# Motherboard_schematic.net
KiCad netlist of a schematic drawn in Altium Designer
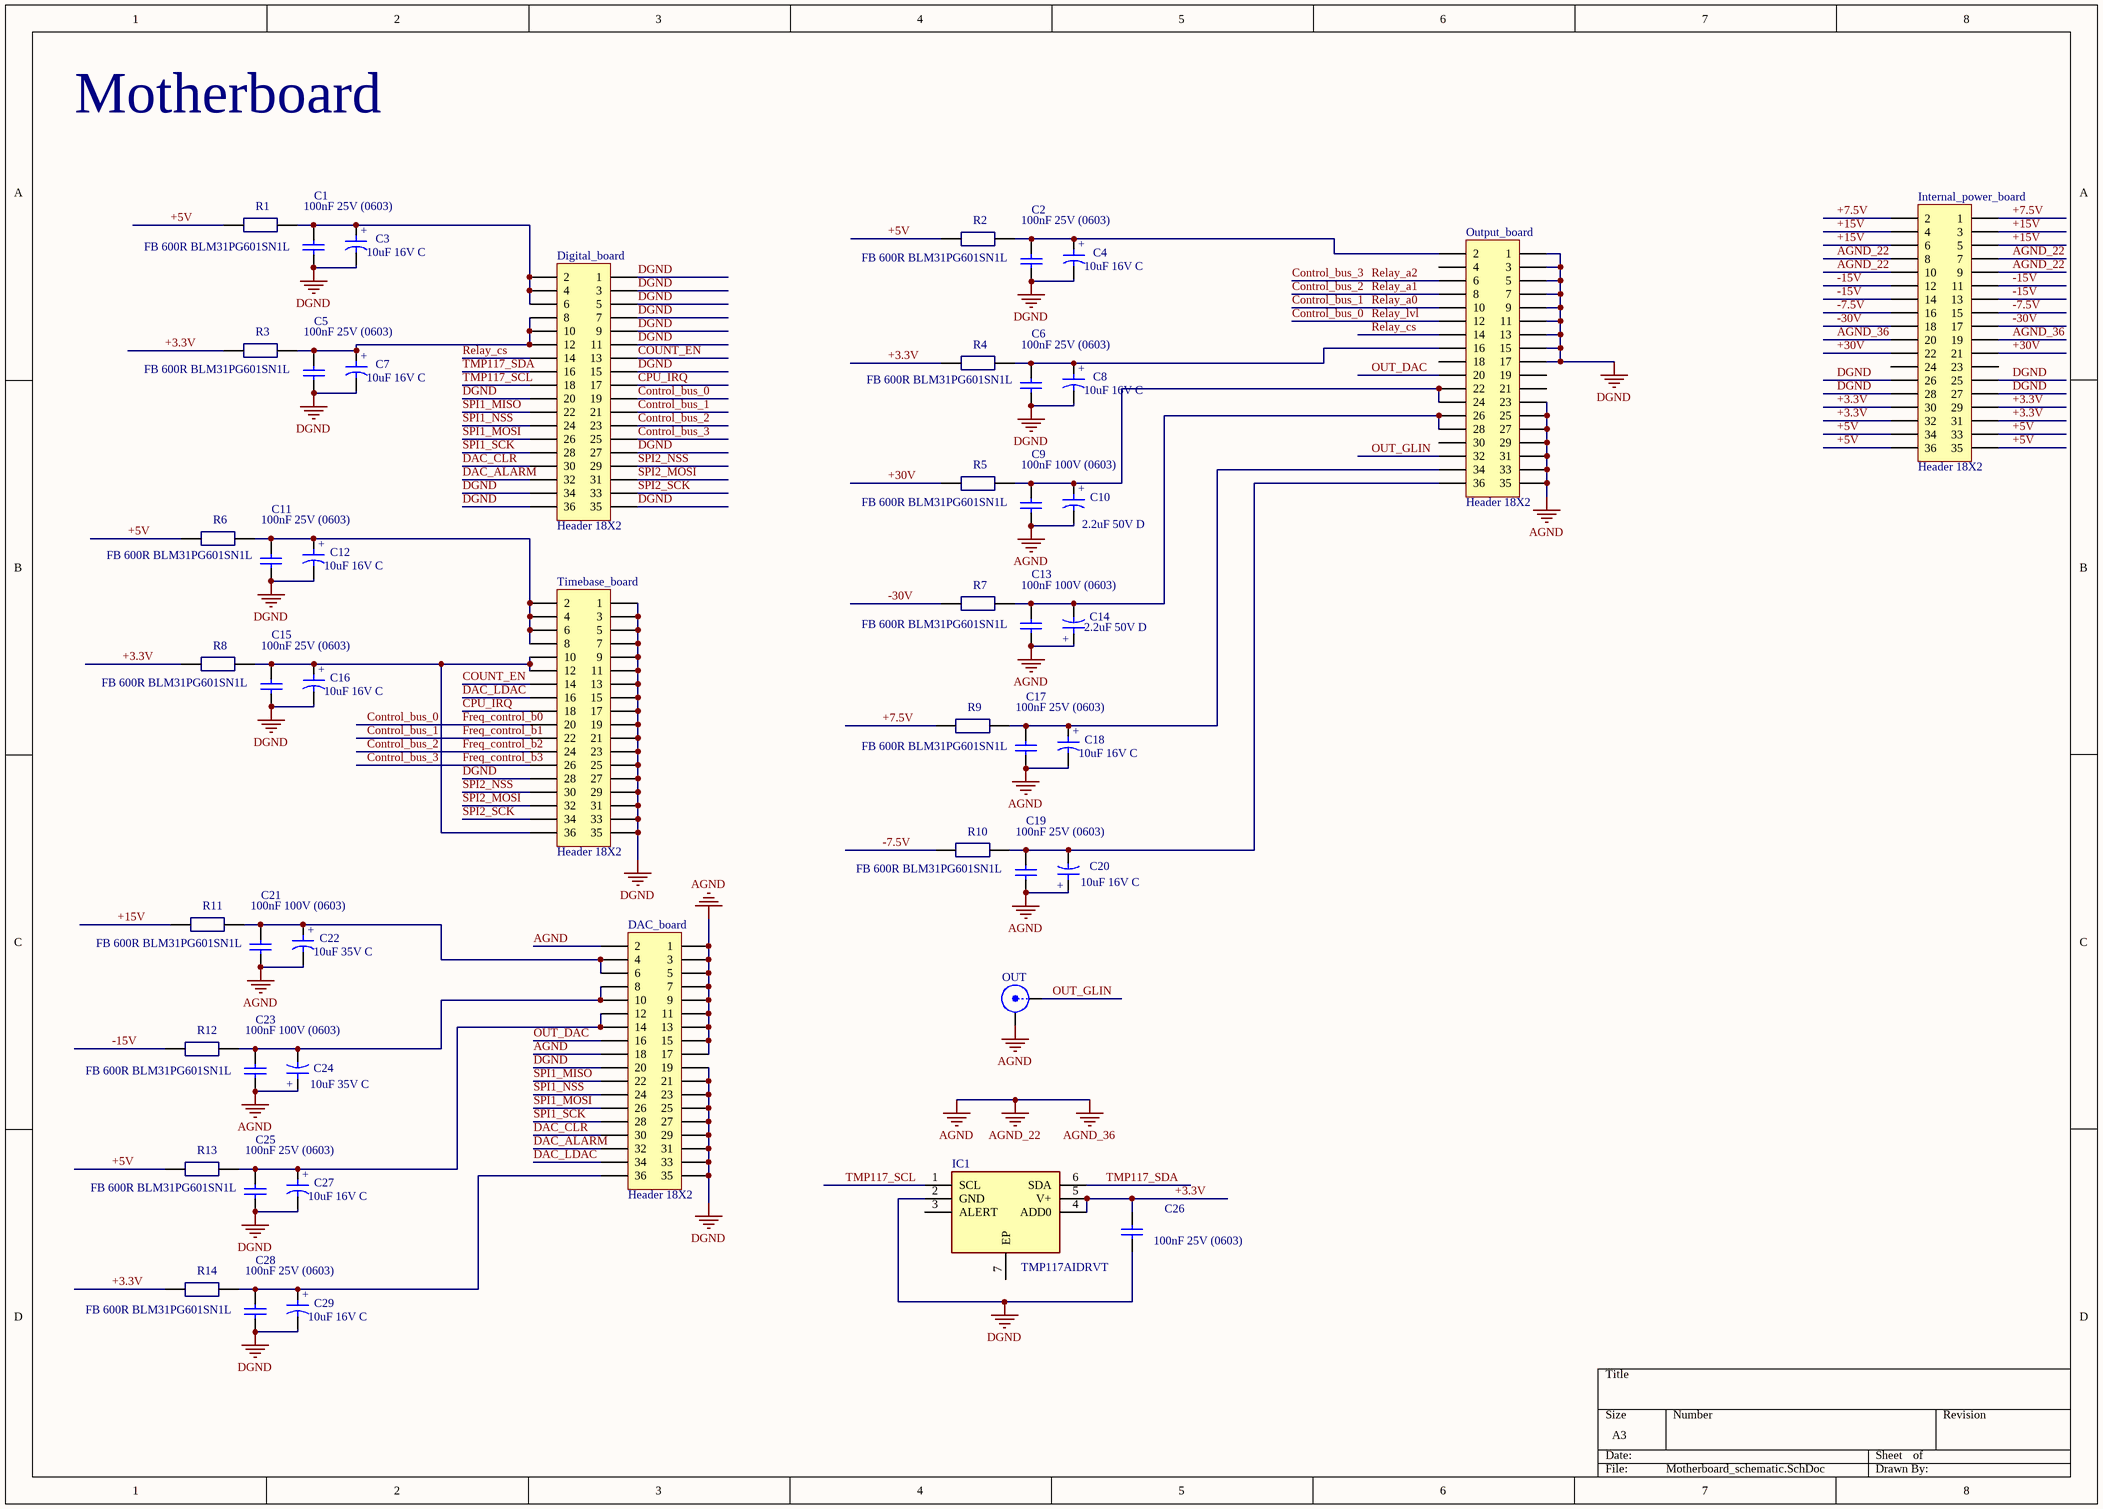
[diagram p0: Motherboard_schematic.SchDoc]

(export (version "E")
  (design (tool "Eeschema 10.0.6"))
  (components
    (comp (ref "C1")
      (value "100nF 25V (0603)")
      (footprint "CAP 0603")
      (description "Capacitor (Semiconductor SIM Model)")
      (fields (field (name "PUBLISHER") "Altium Limited"))
      (libsource (lib "Miscellaneous Devices") (part "Cap Semi"))
    )
    (comp (ref "C2")
      (value "100nF 25V (0603)")
      (footprint "CAP 0603")
      (description "Capacitor (Semiconductor SIM Model)")
      (fields (field (name "PUBLISHER") "Altium Limited"))
      (libsource (lib "Miscellaneous Devices") (part "Cap Semi"))
    )
    (comp (ref "C3")
      (value "10uF 16V C")
      (footprint "CAPMP6032X280N")
      (description "Polarised capacitor")
      (fields
        (field (name "PART NUMBER") "CTE6032-28_10UF_25V_10%_LESR0500")
        (field (name "VOLTAGE") "25V")
        (field (name "AUTHOR") "CERN DEM JLC")
      )
      (libsource (lib "Capacitors") (part "Capacitor - polarized"))
    )
    (comp (ref "C4")
      (value "10uF 16V C")
      (footprint "CAPMP6032X280N")
      (description "Polarised capacitor")
      (fields
        (field (name "PART NUMBER") "CTE6032-28_10UF_25V_10%_LESR0500")
        (field (name "VOLTAGE") "25V")
        (field (name "AUTHOR") "CERN DEM JLC")
      )
      (libsource (lib "Capacitors") (part "Capacitor - polarized"))
    )
    (comp (ref "C5")
      (value "100nF 25V (0603)")
      (footprint "CAP 0603")
      (description "Capacitor (Semiconductor SIM Model)")
      (fields (field (name "PUBLISHER") "Altium Limited"))
      (libsource (lib "Miscellaneous Devices") (part "Cap Semi"))
    )
    (comp (ref "C6")
      (value "100nF 25V (0603)")
      (footprint "CAP 0603")
      (description "Capacitor (Semiconductor SIM Model)")
      (fields (field (name "PUBLISHER") "Altium Limited"))
      (libsource (lib "Miscellaneous Devices") (part "Cap Semi"))
    )
    (comp (ref "C7")
      (value "10uF 16V C")
      (footprint "CAPMP6032X280N")
      (description "Polarised capacitor")
      (fields
        (field (name "PART NUMBER") "CTE6032-28_10UF_25V_10%_LESR0500")
        (field (name "VOLTAGE") "25V")
        (field (name "AUTHOR") "CERN DEM JLC")
      )
      (libsource (lib "Capacitors") (part "Capacitor - polarized"))
    )
    (comp (ref "C8")
      (value "10uF 16V C")
      (footprint "CAPMP6032X280N")
      (description "Polarised capacitor")
      (fields
        (field (name "PART NUMBER") "CTE6032-28_10UF_25V_10%_LESR0500")
        (field (name "VOLTAGE") "25V")
        (field (name "AUTHOR") "CERN DEM JLC")
      )
      (libsource (lib "Capacitors") (part "Capacitor - polarized"))
    )
    (comp (ref "C9")
      (value "100nF 100V (0603)")
      (footprint "CAP 0603")
      (description "Capacitor (Semiconductor SIM Model)")
      (fields (field (name "PUBLISHER") "Altium Limited"))
      (libsource (lib "Miscellaneous Devices") (part "Cap Semi"))
    )
    (comp (ref "C10")
      (value "2.2uF 50V D")
      (footprint "CAPMP7343X310N")
      (description "Polarised capacitor")
      (fields
        (field (name "PART NUMBER") "CTE7343-31_22UF_35V_20%_LESR0400")
        (field (name "VOLTAGE") "35V")
        (field (name "AUTHOR") "CERN DEM MR")
      )
      (libsource (lib "Capacitors") (part "Capacitor - polarized"))
    )
    (comp (ref "C11")
      (value "100nF 25V (0603)")
      (footprint "CAP 0603")
      (description "Capacitor (Semiconductor SIM Model)")
      (fields (field (name "PUBLISHER") "Altium Limited"))
      (libsource (lib "Miscellaneous Devices") (part "Cap Semi"))
    )
    (comp (ref "C12")
      (value "10uF 16V C")
      (footprint "CAPMP6032X280N")
      (description "Polarised capacitor")
      (fields
        (field (name "PART NUMBER") "CTE6032-28_10UF_25V_10%_LESR0500")
        (field (name "VOLTAGE") "25V")
        (field (name "AUTHOR") "CERN DEM JLC")
      )
      (libsource (lib "Capacitors") (part "Capacitor - polarized"))
    )
    (comp (ref "C13")
      (value "100nF 100V (0603)")
      (footprint "CAP 0603")
      (description "Capacitor (Semiconductor SIM Model)")
      (fields (field (name "PUBLISHER") "Altium Limited"))
      (libsource (lib "Miscellaneous Devices") (part "Cap Semi"))
    )
    (comp (ref "C14")
      (value "2.2uF 50V D")
      (footprint "CAPMP7343X310N")
      (description "Polarised capacitor")
      (fields
        (field (name "PART NUMBER") "CTE7343-31_22UF_35V_20%_LESR0400")
        (field (name "VOLTAGE") "35V")
        (field (name "AUTHOR") "CERN DEM MR")
      )
      (libsource (lib "Capacitors") (part "Capacitor - polarized"))
    )
    (comp (ref "C15")
      (value "100nF 25V (0603)")
      (footprint "CAP 0603")
      (description "Capacitor (Semiconductor SIM Model)")
      (fields (field (name "PUBLISHER") "Altium Limited"))
      (libsource (lib "Miscellaneous Devices") (part "Cap Semi"))
    )
    (comp (ref "C16")
      (value "10uF 16V C")
      (footprint "CAPMP6032X280N")
      (description "Polarised capacitor")
      (fields
        (field (name "PART NUMBER") "CTE6032-28_10UF_25V_10%_LESR0500")
        (field (name "VOLTAGE") "25V")
        (field (name "AUTHOR") "CERN DEM JLC")
      )
      (libsource (lib "Capacitors") (part "Capacitor - polarized"))
    )
    (comp (ref "C17")
      (value "100nF 25V (0603)")
      (footprint "CAP 0603")
      (description "Capacitor (Semiconductor SIM Model)")
      (fields (field (name "PUBLISHER") "Altium Limited"))
      (libsource (lib "Miscellaneous Devices") (part "Cap Semi"))
    )
    (comp (ref "C18")
      (value "10uF 16V C")
      (footprint "CAPMP6032X280N")
      (description "Polarised capacitor")
      (fields
        (field (name "PART NUMBER") "CTE6032-28_10UF_25V_10%_LESR0500")
        (field (name "VOLTAGE") "25V")
        (field (name "AUTHOR") "CERN DEM JLC")
      )
      (libsource (lib "Capacitors") (part "Capacitor - polarized"))
    )
    (comp (ref "C19")
      (value "100nF 25V (0603)")
      (footprint "CAP 0603")
      (description "Capacitor (Semiconductor SIM Model)")
      (fields (field (name "PUBLISHER") "Altium Limited"))
      (libsource (lib "Miscellaneous Devices") (part "Cap Semi"))
    )
    (comp (ref "C20")
      (value "10uF 16V C")
      (footprint "CAPMP6032X280N")
      (description "Polarised capacitor")
      (fields
        (field (name "PART NUMBER") "CTE6032-28_10UF_25V_10%_LESR0500")
        (field (name "VOLTAGE") "25V")
        (field (name "AUTHOR") "CERN DEM JLC")
      )
      (libsource (lib "Capacitors") (part "Capacitor - polarized"))
    )
    (comp (ref "C21")
      (value "100nF 100V (0603)")
      (footprint "CAP 0603")
      (description "Capacitor (Semiconductor SIM Model)")
      (fields (field (name "PUBLISHER") "Altium Limited"))
      (libsource (lib "Miscellaneous Devices") (part "Cap Semi"))
    )
    (comp (ref "C22")
      (value "10uF 35V C")
      (footprint "CAPMP6032X280N")
      (description "Polarised capacitor")
      (fields
        (field (name "PART NUMBER") "CTE6032-28_10UF_25V_10%_LESR0500")
        (field (name "VOLTAGE") "25V")
        (field (name "AUTHOR") "CERN DEM JLC")
      )
      (libsource (lib "Capacitors") (part "Capacitor - polarized"))
    )
    (comp (ref "C23")
      (value "100nF 100V (0603)")
      (footprint "CAP 0603")
      (description "Capacitor (Semiconductor SIM Model)")
      (fields (field (name "PUBLISHER") "Altium Limited"))
      (libsource (lib "Miscellaneous Devices") (part "Cap Semi"))
    )
    (comp (ref "C24")
      (value "10uF 35V C")
      (footprint "CAPMP6032X280N")
      (description "Polarised capacitor")
      (fields
        (field (name "PART NUMBER") "CTE6032-28_10UF_25V_10%_LESR0500")
        (field (name "VOLTAGE") "25V")
        (field (name "AUTHOR") "CERN DEM JLC")
      )
      (libsource (lib "Capacitors") (part "Capacitor - polarized"))
    )
    (comp (ref "C25")
      (value "100nF 25V (0603)")
      (footprint "CAP 0603")
      (description "Capacitor (Semiconductor SIM Model)")
      (fields (field (name "PUBLISHER") "Altium Limited"))
      (libsource (lib "Miscellaneous Devices") (part "Cap Semi"))
    )
    (comp (ref "C26")
      (value "100nF 25V (0603)")
      (footprint "CAP 0603")
      (description "Capacitor (Semiconductor SIM Model)")
      (fields (field (name "PUBLISHER") "Altium Limited"))
      (libsource (lib "Miscellaneous Devices") (part "Cap Semi"))
    )
    (comp (ref "C27")
      (value "10uF 16V C")
      (footprint "CAPMP6032X280N")
      (description "Polarised capacitor")
      (fields
        (field (name "PART NUMBER") "CTE6032-28_10UF_25V_10%_LESR0500")
        (field (name "VOLTAGE") "25V")
        (field (name "AUTHOR") "CERN DEM JLC")
      )
      (libsource (lib "Capacitors") (part "Capacitor - polarized"))
    )
    (comp (ref "C28")
      (value "100nF 25V (0603)")
      (footprint "CAP 0603")
      (description "Capacitor (Semiconductor SIM Model)")
      (fields (field (name "PUBLISHER") "Altium Limited"))
      (libsource (lib "Miscellaneous Devices") (part "Cap Semi"))
    )
    (comp (ref "C29")
      (value "10uF 16V C")
      (footprint "CAPMP6032X280N")
      (description "Polarised capacitor")
      (fields
        (field (name "PART NUMBER") "CTE6032-28_10UF_25V_10%_LESR0500")
        (field (name "VOLTAGE") "25V")
        (field (name "AUTHOR") "CERN DEM JLC")
      )
      (libsource (lib "Capacitors") (part "Capacitor - polarized"))
    )
    (comp (ref "DAC_board")
      (value "Header 18X2")
      (footprint "HDR2X18")
      (description "Header, 18-Pin, Dual row")
      (fields (field (name "PUBLISHER") "Altium Limited"))
      (libsource (lib "Miscellaneous Connectors") (part "Header 18X2"))
    )
    (comp (ref "Digital_board")
      (value "Header 18X2")
      (footprint "HDR2X18")
      (description "Header, 18-Pin, Dual row")
      (fields (field (name "PUBLISHER") "Altium Limited"))
      (libsource (lib "Miscellaneous Connectors") (part "Header 18X2"))
    )
    (comp (ref "IC1")
      (value "TMP117AIDRVT")
      (footprint "SamacSys:SON65P200X200X80-7N-D")
      (description "Integrated Circuit")
      (fields (field (name "MOUSER PART NUMBER") "595-TMP117AIDRVT"))
      (libsource (lib "*") (part "TMP117AIDRVT"))
    )
    (comp (ref "Internal_power_board")
      (value "Header 18X2")
      (footprint "HDR2X18")
      (description "Header, 18-Pin, Dual row")
      (fields (field (name "PUBLISHER") "Altium Limited"))
      (libsource (lib "Miscellaneous Connectors") (part "Header 18X2"))
    )
    (comp (ref "OUT")
      (value "SMB")
      (footprint "SMB_V-RJ45")
      (description "SMB Straight Connector")
      (fields (field (name "PUBLISHER") "Altium Limited"))
      (libsource (lib "Miscellaneous Connectors") (part "SMB"))
    )
    (comp (ref "Output_board")
      (value "Header 18X2")
      (footprint "HDR2X18")
      (description "Header, 18-Pin, Dual row")
      (fields (field (name "PUBLISHER") "Altium Limited"))
      (libsource (lib "Miscellaneous Connectors") (part "Header 18X2"))
    )
    (comp (ref "R1")
      (value "FB 600R BLM31PG601SN1L")
      (footprint "C1206")
      (libsource (lib "Микрон-3") (part "Resistor 0805"))
    )
    (comp (ref "R2")
      (value "FB 600R BLM31PG601SN1L")
      (footprint "C1206")
      (libsource (lib "Микрон-3") (part "Resistor 0805"))
    )
    (comp (ref "R3")
      (value "FB 600R BLM31PG601SN1L")
      (footprint "C1206")
      (libsource (lib "Микрон-3") (part "Resistor 0805"))
    )
    (comp (ref "R4")
      (value "FB 600R BLM31PG601SN1L")
      (footprint "C1206")
      (libsource (lib "Микрон-3") (part "Resistor 0805"))
    )
    (comp (ref "R5")
      (value "FB 600R BLM31PG601SN1L")
      (footprint "C1206")
      (libsource (lib "Микрон-3") (part "Resistor 0805"))
    )
    (comp (ref "R6")
      (value "FB 600R BLM31PG601SN1L")
      (footprint "C1206")
      (libsource (lib "Микрон-3") (part "Resistor 0805"))
    )
    (comp (ref "R7")
      (value "FB 600R BLM31PG601SN1L")
      (footprint "C1206")
      (libsource (lib "Микрон-3") (part "Resistor 0805"))
    )
    (comp (ref "R8")
      (value "FB 600R BLM31PG601SN1L")
      (footprint "C1206")
      (libsource (lib "Микрон-3") (part "Resistor 0805"))
    )
    (comp (ref "R9")
      (value "FB 600R BLM31PG601SN1L")
      (footprint "C1206")
      (libsource (lib "Микрон-3") (part "Resistor 0805"))
    )
    (comp (ref "R10")
      (value "FB 600R BLM31PG601SN1L")
      (footprint "C1206")
      (libsource (lib "Микрон-3") (part "Resistor 0805"))
    )
    (comp (ref "R11")
      (value "FB 600R BLM31PG601SN1L")
      (footprint "C1206")
      (libsource (lib "Микрон-3") (part "Resistor 0805"))
    )
    (comp (ref "R12")
      (value "FB 600R BLM31PG601SN1L")
      (footprint "C1206")
      (libsource (lib "Микрон-3") (part "Resistor 0805"))
    )
    (comp (ref "R13")
      (value "FB 600R BLM31PG601SN1L")
      (footprint "C1206")
      (libsource (lib "Микрон-3") (part "Resistor 0805"))
    )
    (comp (ref "R14")
      (value "FB 600R BLM31PG601SN1L")
      (footprint "C1206")
      (libsource (lib "Микрон-3") (part "Resistor 0805"))
    )
    (comp (ref "Timebase_board")
      (value "Header 18X2")
      (footprint "HDR2X18")
      (description "Header, 18-Pin, Dual row")
      (fields (field (name "PUBLISHER") "Altium Limited"))
      (libsource (lib "Miscellaneous Connectors") (part "Header 18X2"))
    )
  )
  (nets
    (net (code "1") (name "/+3.3V") (class "Default")
      (node (ref "C26") (pin "1") (pinfunction "1_1") (pintype "passive"))
      (node (ref "IC1") (pin "4") (pinfunction "ADD0_4") (pintype "passive"))
      (node (ref "IC1") (pin "5") (pinfunction "V+_5") (pintype "passive"))
      (node (ref "Internal_power_board") (pin "29") (pinfunction "29_29") (pintype "passive"))
      (node (ref "Internal_power_board") (pin "30") (pinfunction "30_30") (pintype "passive"))
      (node (ref "Internal_power_board") (pin "31") (pinfunction "31_31") (pintype "passive"))
      (node (ref "Internal_power_board") (pin "32") (pinfunction "32_32") (pintype "passive"))
      (node (ref "R14") (pin "2") (pinfunction "2_2") (pintype "passive"))
      (node (ref "R3") (pin "2") (pinfunction "2_2") (pintype "passive"))
      (node (ref "R4") (pin "2") (pinfunction "2_2") (pintype "passive"))
      (node (ref "R8") (pin "2") (pinfunction "2_2") (pintype "passive"))
    )
    (net (code "2") (name "/+5V") (class "Default")
      (node (ref "Internal_power_board") (pin "33") (pinfunction "33_33") (pintype "passive"))
      (node (ref "Internal_power_board") (pin "34") (pinfunction "34_34") (pintype "passive"))
      (node (ref "Internal_power_board") (pin "35") (pinfunction "35_35") (pintype "passive"))
      (node (ref "Internal_power_board") (pin "36") (pinfunction "36_36") (pintype "passive"))
      (node (ref "R1") (pin "2") (pinfunction "2_2") (pintype "passive"))
      (node (ref "R13") (pin "2") (pinfunction "2_2") (pintype "passive"))
      (node (ref "R2") (pin "2") (pinfunction "2_2") (pintype "passive"))
      (node (ref "R6") (pin "2") (pinfunction "2_2") (pintype "passive"))
    )
    (net (code "3") (name "/+7.5V") (class "Default")
      (node (ref "Internal_power_board") (pin "1") (pinfunction "1_1") (pintype "passive"))
      (node (ref "Internal_power_board") (pin "2") (pinfunction "2_2") (pintype "passive"))
      (node (ref "R9") (pin "2") (pinfunction "2_2") (pintype "passive"))
    )
    (net (code "4") (name "/+15V") (class "Default")
      (node (ref "Internal_power_board") (pin "3") (pinfunction "3_3") (pintype "passive"))
      (node (ref "Internal_power_board") (pin "4") (pinfunction "4_4") (pintype "passive"))
      (node (ref "Internal_power_board") (pin "5") (pinfunction "5_5") (pintype "passive"))
      (node (ref "Internal_power_board") (pin "6") (pinfunction "6_6") (pintype "passive"))
      (node (ref "R11") (pin "2") (pinfunction "2_2") (pintype "passive"))
    )
    (net (code "5") (name "/+30V") (class "Default")
      (node (ref "Internal_power_board") (pin "21") (pinfunction "21_21") (pintype "passive"))
      (node (ref "Internal_power_board") (pin "22") (pinfunction "22_22") (pintype "passive"))
      (node (ref "R5") (pin "2") (pinfunction "2_2") (pintype "passive"))
    )
    (net (code "6") (name "/-7.5V") (class "Default")
      (node (ref "Internal_power_board") (pin "15") (pinfunction "15_15") (pintype "passive"))
      (node (ref "Internal_power_board") (pin "16") (pinfunction "16_16") (pintype "passive"))
      (node (ref "R10") (pin "2") (pinfunction "2_2") (pintype "passive"))
    )
    (net (code "7") (name "/-15V") (class "Default")
      (node (ref "Internal_power_board") (pin "11") (pinfunction "11_11") (pintype "passive"))
      (node (ref "Internal_power_board") (pin "12") (pinfunction "12_12") (pintype "passive"))
      (node (ref "Internal_power_board") (pin "13") (pinfunction "13_13") (pintype "passive"))
      (node (ref "Internal_power_board") (pin "14") (pinfunction "14_14") (pintype "passive"))
      (node (ref "R12") (pin "2") (pinfunction "2_2") (pintype "passive"))
    )
    (net (code "8") (name "/-30V") (class "Default")
      (node (ref "Internal_power_board") (pin "17") (pinfunction "17_17") (pintype "passive"))
      (node (ref "Internal_power_board") (pin "18") (pinfunction "18_18") (pintype "passive"))
      (node (ref "R7") (pin "2") (pinfunction "2_2") (pintype "passive"))
    )
    (net (code "9") (name "/COUNT_EN") (class "Default")
      (node (ref "Digital_board") (pin "13") (pinfunction "13_13") (pintype "passive"))
      (node (ref "Timebase_board") (pin "14") (pinfunction "14_14") (pintype "passive"))
    )
    (net (code "10") (name "/CPU_IRQ") (class "Default")
      (node (ref "Digital_board") (pin "17") (pinfunction "17_17") (pintype "passive"))
      (node (ref "Timebase_board") (pin "18") (pinfunction "18_18") (pintype "passive"))
    )
    (net (code "11") (name "/Control_bus_0") (class "Default")
      (node (ref "Digital_board") (pin "19") (pinfunction "19_19") (pintype "passive"))
      (node (ref "Output_board") (pin "12") (pinfunction "12_12") (pintype "passive"))
      (node (ref "Timebase_board") (pin "20") (pinfunction "20_20") (pintype "passive"))
    )
    (net (code "12") (name "/Control_bus_1") (class "Default")
      (node (ref "Digital_board") (pin "21") (pinfunction "21_21") (pintype "passive"))
      (node (ref "Output_board") (pin "10") (pinfunction "10_10") (pintype "passive"))
      (node (ref "Timebase_board") (pin "22") (pinfunction "22_22") (pintype "passive"))
    )
    (net (code "13") (name "/Control_bus_2") (class "Default")
      (node (ref "Digital_board") (pin "23") (pinfunction "23_23") (pintype "passive"))
      (node (ref "Output_board") (pin "8") (pinfunction "8_8") (pintype "passive"))
      (node (ref "Timebase_board") (pin "24") (pinfunction "24_24") (pintype "passive"))
    )
    (net (code "14") (name "/Control_bus_3") (class "Default")
      (node (ref "Digital_board") (pin "25") (pinfunction "25_25") (pintype "passive"))
      (node (ref "Output_board") (pin "6") (pinfunction "6_6") (pintype "passive"))
      (node (ref "Timebase_board") (pin "26") (pinfunction "26_26") (pintype "passive"))
    )
    (net (code "15") (name "/DAC_ALARM") (class "Default")
      (node (ref "DAC_board") (pin "32") (pinfunction "32_32") (pintype "passive"))
      (node (ref "Digital_board") (pin "32") (pinfunction "32_32") (pintype "passive"))
    )
    (net (code "16") (name "/DAC_CLR") (class "Default")
      (node (ref "DAC_board") (pin "30") (pinfunction "30_30") (pintype "passive"))
      (node (ref "Digital_board") (pin "30") (pinfunction "30_30") (pintype "passive"))
    )
    (net (code "17") (name "/DAC_LDAC") (class "Default")
      (node (ref "DAC_board") (pin "34") (pinfunction "34_34") (pintype "passive"))
      (node (ref "Timebase_board") (pin "16") (pinfunction "16_16") (pintype "passive"))
    )
    (net (code "18") (name "/OUT_DAC") (class "Default")
      (node (ref "DAC_board") (pin "16") (pinfunction "16_16") (pintype "passive"))
      (node (ref "Output_board") (pin "20") (pinfunction "20_20") (pintype "passive"))
    )
    (net (code "19") (name "/OUT_GLIN") (class "Default")
      (node (ref "OUT") (pin "1") (pinfunction "X_1") (pintype "passive"))
      (node (ref "Output_board") (pin "32") (pinfunction "32_32") (pintype "passive"))
    )
    (net (code "20") (name "/Relay_cs") (class "Default")
      (node (ref "Digital_board") (pin "14") (pinfunction "14_14") (pintype "passive"))
      (node (ref "Output_board") (pin "14") (pinfunction "14_14") (pintype "passive"))
    )
    (net (code "21") (name "/SPI1_MISO") (class "Default")
      (node (ref "DAC_board") (pin "22") (pinfunction "22_22") (pintype "passive"))
      (node (ref "Digital_board") (pin "22") (pinfunction "22_22") (pintype "passive"))
    )
    (net (code "22") (name "/SPI1_MOSI") (class "Default")
      (node (ref "DAC_board") (pin "26") (pinfunction "26_26") (pintype "passive"))
      (node (ref "Digital_board") (pin "26") (pinfunction "26_26") (pintype "passive"))
    )
    (net (code "23") (name "/SPI1_NSS") (class "Default")
      (node (ref "DAC_board") (pin "24") (pinfunction "24_24") (pintype "passive"))
      (node (ref "Digital_board") (pin "24") (pinfunction "24_24") (pintype "passive"))
    )
    (net (code "24") (name "/SPI1_SCK") (class "Default")
      (node (ref "DAC_board") (pin "28") (pinfunction "28_28") (pintype "passive"))
      (node (ref "Digital_board") (pin "28") (pinfunction "28_28") (pintype "passive"))
    )
    (net (code "25") (name "/SPI2_MOSI") (class "Default")
      (node (ref "Digital_board") (pin "31") (pinfunction "31_31") (pintype "passive"))
      (node (ref "Timebase_board") (pin "32") (pinfunction "32_32") (pintype "passive"))
    )
    (net (code "26") (name "/SPI2_NSS") (class "Default")
      (node (ref "Digital_board") (pin "29") (pinfunction "29_29") (pintype "passive"))
      (node (ref "Timebase_board") (pin "30") (pinfunction "30_30") (pintype "passive"))
    )
    (net (code "27") (name "/SPI2_SCK") (class "Default")
      (node (ref "Digital_board") (pin "33") (pinfunction "33_33") (pintype "passive"))
      (node (ref "Timebase_board") (pin "34") (pinfunction "34_34") (pintype "passive"))
    )
    (net (code "28") (name "/TMP117_SCL") (class "Default")
      (node (ref "Digital_board") (pin "18") (pinfunction "18_18") (pintype "passive"))
      (node (ref "IC1") (pin "1") (pinfunction "SCL_1") (pintype "passive"))
    )
    (net (code "29") (name "/TMP117_SDA") (class "Default")
      (node (ref "Digital_board") (pin "16") (pinfunction "16_16") (pintype "passive"))
      (node (ref "IC1") (pin "6") (pinfunction "SDA_6") (pintype "passive"))
    )
    (net (code "30") (name "AGND") (class "Default")
      (node (ref "C10") (pin "2") (pinfunction "2_2") (pintype "passive"))
      (node (ref "C13") (pin "2") (pinfunction "2_2") (pintype "passive"))
      (node (ref "C14") (pin "1") (pinfunction "1_1") (pintype "passive"))
      (node (ref "C17") (pin "2") (pinfunction "2_2") (pintype "passive"))
      (node (ref "C18") (pin "2") (pinfunction "2_2") (pintype "passive"))
      (node (ref "C19") (pin "2") (pinfunction "2_2") (pintype "passive"))
      (node (ref "C20") (pin "1") (pinfunction "1_1") (pintype "passive"))
      (node (ref "C21") (pin "2") (pinfunction "2_2") (pintype "passive"))
      (node (ref "C22") (pin "2") (pinfunction "2_2") (pintype "passive"))
      (node (ref "C23") (pin "2") (pinfunction "2_2") (pintype "passive"))
      (node (ref "C24") (pin "1") (pinfunction "1_1") (pintype "passive"))
      (node (ref "C9") (pin "2") (pinfunction "2_2") (pintype "passive"))
      (node (ref "DAC_board") (pin "1") (pinfunction "1_1") (pintype "passive"))
      (node (ref "DAC_board") (pin "11") (pinfunction "11_11") (pintype "passive"))
      (node (ref "DAC_board") (pin "13") (pinfunction "13_13") (pintype "passive"))
      (node (ref "DAC_board") (pin "15") (pinfunction "15_15") (pintype "passive"))
      (node (ref "DAC_board") (pin "17") (pinfunction "17_17") (pintype "passive"))
      (node (ref "DAC_board") (pin "18") (pinfunction "18_18") (pintype "passive"))
      (node (ref "DAC_board") (pin "2") (pinfunction "2_2") (pintype "passive"))
      (node (ref "DAC_board") (pin "3") (pinfunction "3_3") (pintype "passive"))
      (node (ref "DAC_board") (pin "5") (pinfunction "5_5") (pintype "passive"))
      (node (ref "DAC_board") (pin "7") (pinfunction "7_7") (pintype "passive"))
      (node (ref "DAC_board") (pin "9") (pinfunction "9_9") (pintype "passive"))
      (node (ref "Internal_power_board") (pin "10") (pinfunction "10_10") (pintype "passive"))
      (node (ref "Internal_power_board") (pin "19") (pinfunction "19_19") (pintype "passive"))
      (node (ref "Internal_power_board") (pin "20") (pinfunction "20_20") (pintype "passive"))
      (node (ref "Internal_power_board") (pin "7") (pinfunction "7_7") (pintype "passive"))
      (node (ref "Internal_power_board") (pin "8") (pinfunction "8_8") (pintype "passive"))
      (node (ref "Internal_power_board") (pin "9") (pinfunction "9_9") (pintype "passive"))
      (node (ref "OUT") (pin "2") (pinfunction "Y_2") (pintype "passive"))
      (node (ref "Output_board") (pin "23") (pinfunction "23_23") (pintype "passive"))
      (node (ref "Output_board") (pin "25") (pinfunction "25_25") (pintype "passive"))
      (node (ref "Output_board") (pin "27") (pinfunction "27_27") (pintype "passive"))
      (node (ref "Output_board") (pin "29") (pinfunction "29_29") (pintype "passive"))
      (node (ref "Output_board") (pin "31") (pinfunction "31_31") (pintype "passive"))
      (node (ref "Output_board") (pin "33") (pinfunction "33_33") (pintype "passive"))
      (node (ref "Output_board") (pin "35") (pinfunction "35_35") (pintype "passive"))
    )
    (net (code "31") (name "DGND") (class "Default")
      (node (ref "C1") (pin "2") (pinfunction "2_2") (pintype "passive"))
      (node (ref "C11") (pin "2") (pinfunction "2_2") (pintype "passive"))
      (node (ref "C12") (pin "2") (pinfunction "2_2") (pintype "passive"))
      (node (ref "C15") (pin "2") (pinfunction "2_2") (pintype "passive"))
      (node (ref "C16") (pin "2") (pinfunction "2_2") (pintype "passive"))
      (node (ref "C2") (pin "2") (pinfunction "2_2") (pintype "passive"))
      (node (ref "C25") (pin "2") (pinfunction "2_2") (pintype "passive"))
      (node (ref "C26") (pin "2") (pinfunction "2_2") (pintype "passive"))
      (node (ref "C27") (pin "2") (pinfunction "2_2") (pintype "passive"))
      (node (ref "C28") (pin "2") (pinfunction "2_2") (pintype "passive"))
      (node (ref "C29") (pin "2") (pinfunction "2_2") (pintype "passive"))
      (node (ref "C3") (pin "2") (pinfunction "2_2") (pintype "passive"))
      (node (ref "C4") (pin "2") (pinfunction "2_2") (pintype "passive"))
      (node (ref "C5") (pin "2") (pinfunction "2_2") (pintype "passive"))
      (node (ref "C6") (pin "2") (pinfunction "2_2") (pintype "passive"))
      (node (ref "C7") (pin "2") (pinfunction "2_2") (pintype "passive"))
      (node (ref "C8") (pin "2") (pinfunction "2_2") (pintype "passive"))
      (node (ref "DAC_board") (pin "19") (pinfunction "19_19") (pintype "passive"))
      (node (ref "DAC_board") (pin "20") (pinfunction "20_20") (pintype "passive"))
      (node (ref "DAC_board") (pin "21") (pinfunction "21_21") (pintype "passive"))
      (node (ref "DAC_board") (pin "23") (pinfunction "23_23") (pintype "passive"))
      (node (ref "DAC_board") (pin "25") (pinfunction "25_25") (pintype "passive"))
      (node (ref "DAC_board") (pin "27") (pinfunction "27_27") (pintype "passive"))
      (node (ref "DAC_board") (pin "29") (pinfunction "29_29") (pintype "passive"))
      (node (ref "DAC_board") (pin "31") (pinfunction "31_31") (pintype "passive"))
      (node (ref "DAC_board") (pin "33") (pinfunction "33_33") (pintype "passive"))
      (node (ref "DAC_board") (pin "35") (pinfunction "35_35") (pintype "passive"))
      (node (ref "Digital_board") (pin "1") (pinfunction "1_1") (pintype "passive"))
      (node (ref "Digital_board") (pin "11") (pinfunction "11_11") (pintype "passive"))
      (node (ref "Digital_board") (pin "15") (pinfunction "15_15") (pintype "passive"))
      (node (ref "Digital_board") (pin "20") (pinfunction "20_20") (pintype "passive"))
      (node (ref "Digital_board") (pin "27") (pinfunction "27_27") (pintype "passive"))
      (node (ref "Digital_board") (pin "3") (pinfunction "3_3") (pintype "passive"))
      (node (ref "Digital_board") (pin "34") (pinfunction "34_34") (pintype "passive"))
      (node (ref "Digital_board") (pin "35") (pinfunction "35_35") (pintype "passive"))
      (node (ref "Digital_board") (pin "36") (pinfunction "36_36") (pintype "passive"))
      (node (ref "Digital_board") (pin "5") (pinfunction "5_5") (pintype "passive"))
      (node (ref "Digital_board") (pin "7") (pinfunction "7_7") (pintype "passive"))
      (node (ref "Digital_board") (pin "9") (pinfunction "9_9") (pintype "passive"))
      (node (ref "IC1") (pin "2") (pinfunction "GND_2") (pintype "passive"))
      (node (ref "Internal_power_board") (pin "25") (pinfunction "25_25") (pintype "passive"))
      (node (ref "Internal_power_board") (pin "26") (pinfunction "26_26") (pintype "passive"))
      (node (ref "Internal_power_board") (pin "27") (pinfunction "27_27") (pintype "passive"))
      (node (ref "Internal_power_board") (pin "28") (pinfunction "28_28") (pintype "passive"))
      (node (ref "Output_board") (pin "1") (pinfunction "1_1") (pintype "passive"))
      (node (ref "Output_board") (pin "11") (pinfunction "11_11") (pintype "passive"))
      (node (ref "Output_board") (pin "13") (pinfunction "13_13") (pintype "passive"))
      (node (ref "Output_board") (pin "15") (pinfunction "15_15") (pintype "passive"))
      (node (ref "Output_board") (pin "17") (pinfunction "17_17") (pintype "passive"))
      (node (ref "Output_board") (pin "3") (pinfunction "3_3") (pintype "passive"))
      (node (ref "Output_board") (pin "5") (pinfunction "5_5") (pintype "passive"))
      (node (ref "Output_board") (pin "7") (pinfunction "7_7") (pintype "passive"))
      (node (ref "Output_board") (pin "9") (pinfunction "9_9") (pintype "passive"))
      (node (ref "Timebase_board") (pin "1") (pinfunction "1_1") (pintype "passive"))
      (node (ref "Timebase_board") (pin "11") (pinfunction "11_11") (pintype "passive"))
      (node (ref "Timebase_board") (pin "13") (pinfunction "13_13") (pintype "passive"))
      (node (ref "Timebase_board") (pin "15") (pinfunction "15_15") (pintype "passive"))
      (node (ref "Timebase_board") (pin "17") (pinfunction "17_17") (pintype "passive"))
      (node (ref "Timebase_board") (pin "19") (pinfunction "19_19") (pintype "passive"))
      (node (ref "Timebase_board") (pin "21") (pinfunction "21_21") (pintype "passive"))
      (node (ref "Timebase_board") (pin "23") (pinfunction "23_23") (pintype "passive"))
      (node (ref "Timebase_board") (pin "25") (pinfunction "25_25") (pintype "passive"))
      (node (ref "Timebase_board") (pin "27") (pinfunction "27_27") (pintype "passive"))
      (node (ref "Timebase_board") (pin "28") (pinfunction "28_28") (pintype "passive"))
      (node (ref "Timebase_board") (pin "29") (pinfunction "29_29") (pintype "passive"))
      (node (ref "Timebase_board") (pin "3") (pinfunction "3_3") (pintype "passive"))
      (node (ref "Timebase_board") (pin "31") (pinfunction "31_31") (pintype "passive"))
      (node (ref "Timebase_board") (pin "33") (pinfunction "33_33") (pintype "passive"))
      (node (ref "Timebase_board") (pin "35") (pinfunction "35_35") (pintype "passive"))
      (node (ref "Timebase_board") (pin "5") (pinfunction "5_5") (pintype "passive"))
      (node (ref "Timebase_board") (pin "7") (pinfunction "7_7") (pintype "passive"))
      (node (ref "Timebase_board") (pin "9") (pinfunction "9_9") (pintype "passive"))
    )
    (net (code "32") (name "Net-(R1-A)") (class "Default")
      (node (ref "C1") (pin "1") (pinfunction "1_1") (pintype "passive"))
      (node (ref "C3") (pin "1") (pinfunction "1_1") (pintype "passive"))
      (node (ref "Digital_board") (pin "2") (pinfunction "2_2") (pintype "passive"))
      (node (ref "Digital_board") (pin "4") (pinfunction "4_4") (pintype "passive"))
      (node (ref "Digital_board") (pin "6") (pinfunction "6_6") (pintype "passive"))
      (node (ref "R1") (pin "1") (pinfunction "A_1") (pintype "passive"))
    )
    (net (code "33") (name "Net-(R2-A)") (class "Default")
      (node (ref "C2") (pin "1") (pinfunction "1_1") (pintype "passive"))
      (node (ref "C4") (pin "1") (pinfunction "1_1") (pintype "passive"))
      (node (ref "Output_board") (pin "2") (pinfunction "2_2") (pintype "passive"))
      (node (ref "R2") (pin "1") (pinfunction "A_1") (pintype "passive"))
    )
    (net (code "34") (name "Net-(R3-A)") (class "Default")
      (node (ref "C5") (pin "1") (pinfunction "1_1") (pintype "passive"))
      (node (ref "C7") (pin "1") (pinfunction "1_1") (pintype "passive"))
      (node (ref "Digital_board") (pin "10") (pinfunction "10_10") (pintype "passive"))
      (node (ref "Digital_board") (pin "12") (pinfunction "12_12") (pintype "passive"))
      (node (ref "Digital_board") (pin "8") (pinfunction "8_8") (pintype "passive"))
      (node (ref "R3") (pin "1") (pinfunction "A_1") (pintype "passive"))
    )
    (net (code "35") (name "Net-(R4-A)") (class "Default")
      (node (ref "C6") (pin "1") (pinfunction "1_1") (pintype "passive"))
      (node (ref "C8") (pin "1") (pinfunction "1_1") (pintype "passive"))
      (node (ref "Output_board") (pin "16") (pinfunction "16_16") (pintype "passive"))
      (node (ref "R4") (pin "1") (pinfunction "A_1") (pintype "passive"))
    )
    (net (code "36") (name "Net-(R5-A)") (class "Default")
      (node (ref "C10") (pin "1") (pinfunction "1_1") (pintype "passive"))
      (node (ref "C9") (pin "1") (pinfunction "1_1") (pintype "passive"))
      (node (ref "Output_board") (pin "22") (pinfunction "22_22") (pintype "passive"))
      (node (ref "Output_board") (pin "24") (pinfunction "24_24") (pintype "passive"))
      (node (ref "R5") (pin "1") (pinfunction "A_1") (pintype "passive"))
    )
    (net (code "37") (name "Net-(R6-A)") (class "Default")
      (node (ref "C11") (pin "1") (pinfunction "1_1") (pintype "passive"))
      (node (ref "C12") (pin "1") (pinfunction "1_1") (pintype "passive"))
      (node (ref "R6") (pin "1") (pinfunction "A_1") (pintype "passive"))
      (node (ref "Timebase_board") (pin "2") (pinfunction "2_2") (pintype "passive"))
      (node (ref "Timebase_board") (pin "4") (pinfunction "4_4") (pintype "passive"))
      (node (ref "Timebase_board") (pin "6") (pinfunction "6_6") (pintype "passive"))
      (node (ref "Timebase_board") (pin "8") (pinfunction "8_8") (pintype "passive"))
    )
    (net (code "38") (name "Net-(R7-A)") (class "Default")
      (node (ref "C13") (pin "1") (pinfunction "1_1") (pintype "passive"))
      (node (ref "C14") (pin "2") (pinfunction "2_2") (pintype "passive"))
      (node (ref "Output_board") (pin "26") (pinfunction "26_26") (pintype "passive"))
      (node (ref "Output_board") (pin "28") (pinfunction "28_28") (pintype "passive"))
      (node (ref "R7") (pin "1") (pinfunction "A_1") (pintype "passive"))
    )
    (net (code "39") (name "Net-(R8-A)") (class "Default")
      (node (ref "C15") (pin "1") (pinfunction "1_1") (pintype "passive"))
      (node (ref "C16") (pin "1") (pinfunction "1_1") (pintype "passive"))
      (node (ref "R8") (pin "1") (pinfunction "A_1") (pintype "passive"))
      (node (ref "Timebase_board") (pin "10") (pinfunction "10_10") (pintype "passive"))
      (node (ref "Timebase_board") (pin "12") (pinfunction "12_12") (pintype "passive"))
      (node (ref "Timebase_board") (pin "36") (pinfunction "36_36") (pintype "passive"))
    )
    (net (code "40") (name "Net-(R9-A)") (class "Default")
      (node (ref "C17") (pin "1") (pinfunction "1_1") (pintype "passive"))
      (node (ref "C18") (pin "1") (pinfunction "1_1") (pintype "passive"))
      (node (ref "Output_board") (pin "34") (pinfunction "34_34") (pintype "passive"))
      (node (ref "R9") (pin "1") (pinfunction "A_1") (pintype "passive"))
    )
    (net (code "41") (name "Net-(R10-A)") (class "Default")
      (node (ref "C19") (pin "1") (pinfunction "1_1") (pintype "passive"))
      (node (ref "C20") (pin "2") (pinfunction "2_2") (pintype "passive"))
      (node (ref "Output_board") (pin "36") (pinfunction "36_36") (pintype "passive"))
      (node (ref "R10") (pin "1") (pinfunction "A_1") (pintype "passive"))
    )
    (net (code "42") (name "Net-(R11-A)") (class "Default")
      (node (ref "C21") (pin "1") (pinfunction "1_1") (pintype "passive"))
      (node (ref "C22") (pin "1") (pinfunction "1_1") (pintype "passive"))
      (node (ref "DAC_board") (pin "4") (pinfunction "4_4") (pintype "passive"))
      (node (ref "DAC_board") (pin "6") (pinfunction "6_6") (pintype "passive"))
      (node (ref "R11") (pin "1") (pinfunction "A_1") (pintype "passive"))
    )
    (net (code "43") (name "Net-(R12-A)") (class "Default")
      (node (ref "C23") (pin "1") (pinfunction "1_1") (pintype "passive"))
      (node (ref "C24") (pin "2") (pinfunction "2_2") (pintype "passive"))
      (node (ref "DAC_board") (pin "10") (pinfunction "10_10") (pintype "passive"))
      (node (ref "DAC_board") (pin "8") (pinfunction "8_8") (pintype "passive"))
      (node (ref "R12") (pin "1") (pinfunction "A_1") (pintype "passive"))
    )
    (net (code "44") (name "Net-(R13-A)") (class "Default")
      (node (ref "C25") (pin "1") (pinfunction "1_1") (pintype "passive"))
      (node (ref "C27") (pin "1") (pinfunction "1_1") (pintype "passive"))
      (node (ref "DAC_board") (pin "12") (pinfunction "12_12") (pintype "passive"))
      (node (ref "DAC_board") (pin "14") (pinfunction "14_14") (pintype "passive"))
      (node (ref "R13") (pin "1") (pinfunction "A_1") (pintype "passive"))
    )
    (net (code "45") (name "Net-(R14-A)") (class "Default")
      (node (ref "C28") (pin "1") (pinfunction "1_1") (pintype "passive"))
      (node (ref "C29") (pin "1") (pinfunction "1_1") (pintype "passive"))
      (node (ref "DAC_board") (pin "36") (pinfunction "36_36") (pintype "passive"))
      (node (ref "R14") (pin "1") (pinfunction "A_1") (pintype "passive"))
    )
    (net (code "46") (name "unconnected-(IC1-ALERT-Pad3)") (class "Default")
      (node (ref "IC1") (pin "3") (pinfunction "ALERT_3") (pintype "passive"))
    )
    (net (code "47") (name "unconnected-(IC1-EP-Pad7)") (class "Default")
      (node (ref "IC1") (pin "7") (pinfunction "EP_7") (pintype "passive"))
    )
    (net (code "48") (name "unconnected-(Internal_power_board-Pad23)") (class "Default")
      (node (ref "Internal_power_board") (pin "23") (pinfunction "23_23") (pintype "passive"))
    )
    (net (code "49") (name "unconnected-(Internal_power_board-Pad24)") (class "Default")
      (node (ref "Internal_power_board") (pin "24") (pinfunction "24_24") (pintype "passive"))
    )
    (net (code "50") (name "unconnected-(Output_board-Pad4)") (class "Default")
      (node (ref "Output_board") (pin "4") (pinfunction "4_4") (pintype "passive"))
    )
    (net (code "51") (name "unconnected-(Output_board-Pad18)") (class "Default")
      (node (ref "Output_board") (pin "18") (pinfunction "18_18") (pintype "passive"))
    )
    (net (code "52") (name "unconnected-(Output_board-Pad19)") (class "Default")
      (node (ref "Output_board") (pin "19") (pinfunction "19_19") (pintype "passive"))
    )
    (net (code "53") (name "unconnected-(Output_board-Pad21)") (class "Default")
      (node (ref "Output_board") (pin "21") (pinfunction "21_21") (pintype "passive"))
    )
    (net (code "54") (name "unconnected-(Output_board-Pad30)") (class "Default")
      (node (ref "Output_board") (pin "30") (pinfunction "30_30") (pintype "passive"))
    )
  )
)
